# strip_12.net
KiCad netlist of a schematic drawn in EAGLE
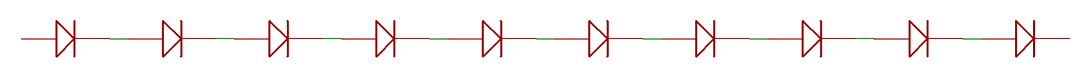
[diagram p0: schematic, sheet 1]

(export (version "E")
  (design (tool "Eeschema 10.0.6"))
  (components
    (comp (ref "U$1")
      (value "JDSTS2.EM-HRHT-XX52-1")
      (footprint "eagle-import:JDSTS2.EM-HRHT-XX52-1")
      (libsource (lib "eagle-import") (part "JDSTS2.EM-HRHT-XX52-1"))
    )
    (comp (ref "U$2")
      (value "JDSTS2.EM-HRHT-XX52-1")
      (footprint "eagle-import:JDSTS2.EM-HRHT-XX52-1")
      (libsource (lib "eagle-import") (part "JDSTS2.EM-HRHT-XX52-1"))
    )
    (comp (ref "U$3")
      (value "JDSTS2.EM-HRHT-XX52-1")
      (footprint "eagle-import:JDSTS2.EM-HRHT-XX52-1")
      (libsource (lib "eagle-import") (part "JDSTS2.EM-HRHT-XX52-1"))
    )
    (comp (ref "U$4")
      (value "JDSTS2.EM-HRHT-XX52-1")
      (footprint "eagle-import:JDSTS2.EM-HRHT-XX52-1")
      (libsource (lib "eagle-import") (part "JDSTS2.EM-HRHT-XX52-1"))
    )
    (comp (ref "U$5")
      (value "JDSTS2.EM-HRHT-XX52-1")
      (footprint "eagle-import:JDSTS2.EM-HRHT-XX52-1")
      (libsource (lib "eagle-import") (part "JDSTS2.EM-HRHT-XX52-1"))
    )
    (comp (ref "U$6")
      (value "JDSTS2.EM-HRHT-XX52-1")
      (footprint "eagle-import:JDSTS2.EM-HRHT-XX52-1")
      (libsource (lib "eagle-import") (part "JDSTS2.EM-HRHT-XX52-1"))
    )
    (comp (ref "U$7")
      (value "JDSTS2.EM-HRHT-XX52-1")
      (footprint "eagle-import:JDSTS2.EM-HRHT-XX52-1")
      (libsource (lib "eagle-import") (part "JDSTS2.EM-HRHT-XX52-1"))
    )
    (comp (ref "U$8")
      (value "JDSTS2.EM-HRHT-XX52-1")
      (footprint "eagle-import:JDSTS2.EM-HRHT-XX52-1")
      (libsource (lib "eagle-import") (part "JDSTS2.EM-HRHT-XX52-1"))
    )
    (comp (ref "U$9")
      (value "JDSTS2.EM-HRHT-XX52-1")
      (footprint "eagle-import:JDSTS2.EM-HRHT-XX52-1")
      (libsource (lib "eagle-import") (part "JDSTS2.EM-HRHT-XX52-1"))
    )
    (comp (ref "U$10")
      (value "JDSTS2.EM-HRHT-XX52-1")
      (footprint "eagle-import:JDSTS2.EM-HRHT-XX52-1")
      (libsource (lib "eagle-import") (part "JDSTS2.EM-HRHT-XX52-1"))
    )
  )
  (nets
    (net (code "1") (name "Net-(U$1-P$2)") (class "Default")
      (node (ref "U$1") (pin "3V") (pinfunction "P$2_3V") (pintype "bidirectional"))
      (node (ref "U$2") (pin "GND") (pinfunction "P$1_GND") (pintype "bidirectional"))
    )
    (net (code "2") (name "Net-(U$2-P$2)") (class "Default")
      (node (ref "U$2") (pin "3V") (pinfunction "P$2_3V") (pintype "bidirectional"))
      (node (ref "U$3") (pin "GND") (pinfunction "P$1_GND") (pintype "bidirectional"))
    )
    (net (code "3") (name "Net-(U$3-P$2)") (class "Default")
      (node (ref "U$3") (pin "3V") (pinfunction "P$2_3V") (pintype "bidirectional"))
      (node (ref "U$4") (pin "GND") (pinfunction "P$1_GND") (pintype "bidirectional"))
    )
    (net (code "4") (name "Net-(U$4-P$2)") (class "Default")
      (node (ref "U$4") (pin "3V") (pinfunction "P$2_3V") (pintype "bidirectional"))
      (node (ref "U$5") (pin "GND") (pinfunction "P$1_GND") (pintype "bidirectional"))
    )
    (net (code "5") (name "Net-(U$5-P$2)") (class "Default")
      (node (ref "U$5") (pin "3V") (pinfunction "P$2_3V") (pintype "bidirectional"))
      (node (ref "U$6") (pin "GND") (pinfunction "P$1_GND") (pintype "bidirectional"))
    )
    (net (code "6") (name "Net-(U$6-P$2)") (class "Default")
      (node (ref "U$6") (pin "3V") (pinfunction "P$2_3V") (pintype "bidirectional"))
      (node (ref "U$7") (pin "GND") (pinfunction "P$1_GND") (pintype "bidirectional"))
    )
    (net (code "7") (name "Net-(U$7-P$2)") (class "Default")
      (node (ref "U$7") (pin "3V") (pinfunction "P$2_3V") (pintype "bidirectional"))
      (node (ref "U$8") (pin "GND") (pinfunction "P$1_GND") (pintype "bidirectional"))
    )
    (net (code "8") (name "Net-(U$8-P$2)") (class "Default")
      (node (ref "U$8") (pin "3V") (pinfunction "P$2_3V") (pintype "bidirectional"))
      (node (ref "U$9") (pin "GND") (pinfunction "P$1_GND") (pintype "bidirectional"))
    )
    (net (code "9") (name "Net-(U$10-P$1)") (class "Default")
      (node (ref "U$10") (pin "GND") (pinfunction "P$1_GND") (pintype "bidirectional"))
      (node (ref "U$9") (pin "3V") (pinfunction "P$2_3V") (pintype "bidirectional"))
    )
    (net (code "10") (name "unconnected-(U$1-P$1-PadGND)") (class "Default")
      (node (ref "U$1") (pin "GND") (pinfunction "P$1_GND") (pintype "bidirectional"))
    )
    (net (code "11") (name "unconnected-(U$10-P$2-Pad3V)") (class "Default")
      (node (ref "U$10") (pin "3V") (pinfunction "P$2_3V") (pintype "bidirectional"))
    )
  )
)
